# MCU.net
KiCad netlist of a schematic drawn in Altium Designer
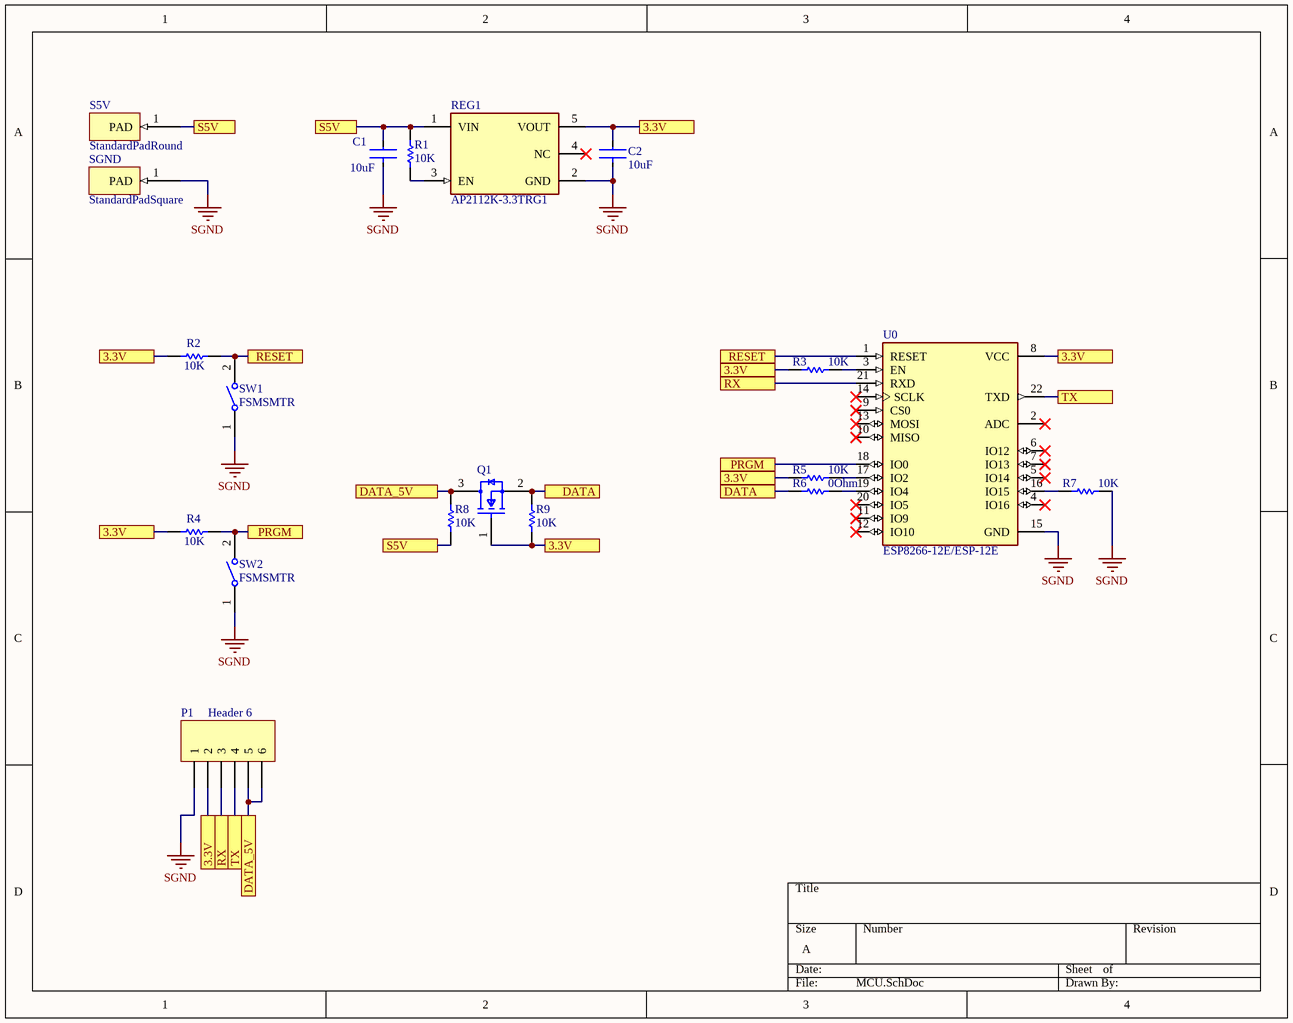
[diagram p0: MCU.SchDoc]

(export (version "E")
  (design (tool "Eeschema 10.0.6"))
  (components
    (comp (ref "C1")
      (value "10uF")
      (footprint "FP-CC0805-0_85-MFG")
      (description "CAP CER 1UF 10V X7R 0805")
      (fields
        (field (name "MANUFACTURER") "Yageo")
        (field (name "OCTOPART") "https://octopart.com/cc0805kkx7r6bb105-yageo-42522859")
      )
      (libsource (lib "Altium Content Vault") (part "11868f565c42a9108669ba33697ecf6"))
    )
    (comp (ref "C2")
      (value "10uF")
      (footprint "FP-CC0805-0_85-MFG")
      (description "CAP CER 1UF 10V X7R 0805")
      (fields
        (field (name "MANUFACTURER") "Yageo")
        (field (name "OCTOPART") "https://octopart.com/cc0805kkx7r6bb105-yageo-42522859")
      )
      (libsource (lib "Altium Content Vault") (part "11868f565c42a9108669ba33697ecf6"))
    )
    (comp (ref "P1")
      (value "Header 6")
      (footprint "HDR1X6")
      (description "Header, 6-Pin")
      (fields (field (name "PUBLISHER") "Altium Limited"))
      (libsource (lib "Gannon University") (part "Symbol"))
    )
    (comp (ref "Q1")
      (value "BSS138")
      (footprint "FP-318-08-IPC_B")
      (description "MOSFET N-CH 50V 220MA SOT-23")
      (libsource (lib "Altium Content Vault") (part "3b9c635fedb024a5347a57b145af9cc"))
    )
    (comp (ref "R1")
      (value "10K")
      (footprint "RESC2013X50X30LL20T20")
      (description "0805")
      (fields (field (name "MANUFACTURER") "Vishay Dale") (field (name "PART NUMBER") "CRCW08050000Z0EA"))
      (libsource (lib "Altium Content Vault") (part "RES"))
    )
    (comp (ref "R2")
      (value "10K")
      (footprint "RESC2013X50X30LL20T20")
      (description "0805")
      (fields (field (name "MANUFACTURER") "Vishay Dale") (field (name "PART NUMBER") "CRCW08050000Z0EA"))
      (libsource (lib "Altium Content Vault") (part "RES"))
    )
    (comp (ref "R3")
      (value "10K")
      (footprint "RESC2013X50X30LL20T20")
      (description "0805")
      (fields (field (name "MANUFACTURER") "Vishay Dale") (field (name "PART NUMBER") "CRCW08050000Z0EA"))
      (libsource (lib "Altium Content Vault") (part "RES"))
    )
    (comp (ref "R4")
      (value "10K")
      (footprint "RESC2013X50X30LL20T20")
      (description "0805")
      (fields (field (name "MANUFACTURER") "Vishay Dale") (field (name "PART NUMBER") "CRCW08050000Z0EA"))
      (libsource (lib "Altium Content Vault") (part "RES"))
    )
    (comp (ref "R5")
      (value "10K")
      (footprint "RESC2013X50X30LL20T20")
      (description "0805")
      (fields (field (name "MANUFACTURER") "Vishay Dale") (field (name "PART NUMBER") "CRCW08050000Z0EA"))
      (libsource (lib "Altium Content Vault") (part "RES"))
    )
    (comp (ref "R6")
      (value "0Ohm")
      (footprint "RESC2013X50X30LL20T20")
      (description "0805")
      (fields (field (name "MANUFACTURER") "Vishay Dale") (field (name "PART NUMBER") "CRCW08050000Z0EA"))
      (libsource (lib "Altium Content Vault") (part "RES"))
    )
    (comp (ref "R7")
      (value "10K")
      (footprint "RESC2013X50X30LL20T20")
      (description "0805")
      (fields (field (name "MANUFACTURER") "Vishay Dale") (field (name "PART NUMBER") "CRCW08050000Z0EA"))
      (libsource (lib "Altium Content Vault") (part "RES"))
    )
    (comp (ref "R8")
      (value "10K")
      (footprint "RESC2013X50X30ML20T20")
      (fields (field (name "PART NUMBER") "CRCW0805270RFKEA") (field (name "MANUFACTURER") "Vishay Dale"))
      (libsource (lib "Altium Content Vault") (part "RES"))
    )
    (comp (ref "R9")
      (value "10K")
      (footprint "RESC2013X50X30ML20T20")
      (fields (field (name "PART NUMBER") "CRCW0805270RFKEA") (field (name "MANUFACTURER") "Vishay Dale"))
      (libsource (lib "Altium Content Vault") (part "RES"))
    )
    (comp (ref "REG1")
      (value "AP2112K-3.3TRG1")
      (footprint "FP-SOT25-IPC_A")
      (description "IC REG LINEAR 3.3V 600MA SOT25")
      (libsource (lib "Altium Content Vault") (part "c8ab751aee5229183125ab046a11caa"))
    )
    (comp (ref "S5V")
      (value "StandardPadRound")
      (footprint "StandardPadRound-Footprint-1")
      (description "1.9mm x 1.9mm round pad with a 1mm hole")
      (libsource (lib "Gannon University") (part "StandardPadRound"))
    )
    (comp (ref "SGND")
      (value "StandardPadSquare")
      (footprint "StandardPadSquare-Footprint-1")
      (description "1.9mm X 1.9mm square pad with 1mm hole")
      (libsource (lib "Gannon University") (part "StandardPadSquare"))
    )
    (comp (ref "SW1")
      (value "FSMSMTR")
      (footprint "TECO-FSMSMTR_V")
      (description "FSMSM Push Button Switch, 50 mA, -35 to 85 degC, 2-Pin SMD, RoHS, Tape and Reel")
      (fields (field (name "MANUFACTURER") "TE Connectivity"))
      (libsource (lib "Altium Content Vault") (part "SW-SPST-2_C"))
    )
    (comp (ref "SW2")
      (value "FSMSMTR")
      (footprint "TECO-FSMSMTR_V")
      (description "FSMSM Push Button Switch, 50 mA, -35 to 85 degC, 2-Pin SMD, RoHS, Tape and Reel")
      (fields (field (name "MANUFACTURER") "TE Connectivity"))
      (libsource (lib "Altium Content Vault") (part "SW-SPST-2_C"))
    )
    (comp (ref "U0")
      (value "ESP8266-12E/ESP-12E")
      (footprint "XCVR_ESP8266-12E%2FESP-12E")
      (fields (field (name "MF") "AI-Thinker"))
      (libsource (lib "Gannon University") (part "ESP8266-12E/ESP-12E"))
    )
  )
  (nets
    (net (code "1") (name "/3.3V") (class "Default")
      (node (ref "C2") (pin "2") (pinfunction "2_2") (pintype "passive"))
      (node (ref "P1") (pin "2") (pinfunction "2_2") (pintype "passive"))
      (node (ref "Q1") (pin "1") (pinfunction "G_1") (pintype "passive"))
      (node (ref "R2") (pin "1") (pinfunction "1_1") (pintype "passive"))
      (node (ref "R3") (pin "1") (pinfunction "1_1") (pintype "passive"))
      (node (ref "R4") (pin "1") (pinfunction "1_1") (pintype "passive"))
      (node (ref "R5") (pin "1") (pinfunction "1_1") (pintype "passive"))
      (node (ref "R9") (pin "1") (pinfunction "1_1") (pintype "passive"))
      (node (ref "REG1") (pin "5") (pinfunction "VOUT_5") (pintype "power_in"))
      (node (ref "U0") (pin "8") (pinfunction "VCC_8") (pintype "power_in"))
    )
    (net (code "2") (name "/DATA") (class "Default")
      (node (ref "Q1") (pin "2") (pinfunction "S_2") (pintype "passive"))
      (node (ref "R6") (pin "1") (pinfunction "1_1") (pintype "passive"))
      (node (ref "R9") (pin "2") (pinfunction "2_2") (pintype "passive"))
    )
    (net (code "3") (name "/DATA_5V") (class "Default")
      (node (ref "P1") (pin "5") (pinfunction "5_5") (pintype "passive"))
      (node (ref "P1") (pin "6") (pinfunction "6_6") (pintype "passive"))
      (node (ref "Q1") (pin "3") (pinfunction "D_3") (pintype "passive"))
      (node (ref "R8") (pin "2") (pinfunction "2_2") (pintype "passive"))
    )
    (net (code "4") (name "/PRGM") (class "Default")
      (node (ref "R4") (pin "2") (pinfunction "2_2") (pintype "passive"))
      (node (ref "SW2") (pin "2") (pinfunction "2_2") (pintype "passive"))
      (node (ref "U0") (pin "18") (pinfunction "IO0_18") (pintype "bidirectional"))
    )
    (net (code "5") (name "/RESET") (class "Default")
      (node (ref "R2") (pin "2") (pinfunction "2_2") (pintype "passive"))
      (node (ref "SW1") (pin "2") (pinfunction "2_2") (pintype "passive"))
      (node (ref "U0") (pin "1") (pinfunction "RESET_1") (pintype "input"))
    )
    (net (code "6") (name "/RX") (class "Default")
      (node (ref "P1") (pin "3") (pinfunction "3_3") (pintype "passive"))
      (node (ref "U0") (pin "21") (pinfunction "RXD_21") (pintype "input"))
    )
    (net (code "7") (name "/S5V") (class "Default")
      (node (ref "C1") (pin "2") (pinfunction "2_2") (pintype "passive"))
      (node (ref "R1") (pin "2") (pinfunction "2_2") (pintype "passive"))
      (node (ref "R8") (pin "1") (pinfunction "1_1") (pintype "passive"))
      (node (ref "REG1") (pin "1") (pinfunction "VIN_1") (pintype "power_in"))
      (node (ref "S5V") (pin "1") (pinfunction "PAD_1") (pintype "input"))
    )
    (net (code "8") (name "/TX") (class "Default")
      (node (ref "P1") (pin "4") (pinfunction "4_4") (pintype "passive"))
      (node (ref "U0") (pin "22") (pinfunction "TXD_22") (pintype "output"))
    )
    (net (code "9") (name "Net-(REG1-EN)") (class "Default")
      (node (ref "R1") (pin "1") (pinfunction "1_1") (pintype "passive"))
      (node (ref "REG1") (pin "3") (pinfunction "EN_3") (pintype "input"))
    )
    (net (code "10") (name "Net-(U0-EN)") (class "Default")
      (node (ref "R3") (pin "2") (pinfunction "2_2") (pintype "passive"))
      (node (ref "U0") (pin "3") (pinfunction "EN_3") (pintype "input"))
    )
    (net (code "11") (name "Net-(U0-IO2)") (class "Default")
      (node (ref "R5") (pin "2") (pinfunction "2_2") (pintype "passive"))
      (node (ref "U0") (pin "17") (pinfunction "IO2_17") (pintype "bidirectional"))
    )
    (net (code "12") (name "Net-(U0-IO4)") (class "Default")
      (node (ref "R6") (pin "2") (pinfunction "2_2") (pintype "passive"))
      (node (ref "U0") (pin "19") (pinfunction "IO4_19") (pintype "bidirectional"))
    )
    (net (code "13") (name "Net-(U0-IO15)") (class "Default")
      (node (ref "R7") (pin "1") (pinfunction "1_1") (pintype "passive"))
      (node (ref "U0") (pin "16") (pinfunction "IO15_16") (pintype "bidirectional"))
    )
    (net (code "14") (name "SGND") (class "Default")
      (node (ref "C1") (pin "1") (pinfunction "1_1") (pintype "passive"))
      (node (ref "C2") (pin "1") (pinfunction "1_1") (pintype "passive"))
      (node (ref "P1") (pin "1") (pinfunction "1_1") (pintype "passive"))
      (node (ref "R7") (pin "2") (pinfunction "2_2") (pintype "passive"))
      (node (ref "REG1") (pin "2") (pinfunction "GND_2") (pintype "power_in"))
      (node (ref "SGND") (pin "1") (pinfunction "PAD_1") (pintype "input"))
      (node (ref "SW1") (pin "1") (pinfunction "1_1") (pintype "passive"))
      (node (ref "SW2") (pin "1") (pinfunction "1_1") (pintype "passive"))
      (node (ref "U0") (pin "15") (pinfunction "GND_15") (pintype "power_in"))
    )
    (net (code "15") (name "unconnected-(REG1-NC-Pad4)") (class "Default")
      (node (ref "REG1") (pin "4") (pinfunction "NC_4") (pintype "passive+no_connect"))
    )
    (net (code "16") (name "unconnected-(U0-ADC-Pad2)") (class "Default")
      (node (ref "U0") (pin "2") (pinfunction "ADC_2") (pintype "passive+no_connect"))
    )
    (net (code "17") (name "unconnected-(U0-CS0-Pad9)") (class "Default")
      (node (ref "U0") (pin "9") (pinfunction "CS0_9") (pintype "input+no_connect"))
    )
    (net (code "18") (name "unconnected-(U0-IO5-Pad20)") (class "Default")
      (node (ref "U0") (pin "20") (pinfunction "IO5_20") (pintype "bidirectional+no_connect"))
    )
    (net (code "19") (name "unconnected-(U0-IO9-Pad11)") (class "Default")
      (node (ref "U0") (pin "11") (pinfunction "IO9_11") (pintype "bidirectional+no_connect"))
    )
    (net (code "20") (name "unconnected-(U0-IO10-Pad12)") (class "Default")
      (node (ref "U0") (pin "12") (pinfunction "IO10_12") (pintype "bidirectional+no_connect"))
    )
    (net (code "21") (name "unconnected-(U0-IO12-Pad6)") (class "Default")
      (node (ref "U0") (pin "6") (pinfunction "IO12_6") (pintype "bidirectional+no_connect"))
    )
    (net (code "22") (name "unconnected-(U0-IO13-Pad7)") (class "Default")
      (node (ref "U0") (pin "7") (pinfunction "IO13_7") (pintype "bidirectional+no_connect"))
    )
    (net (code "23") (name "unconnected-(U0-IO14-Pad5)") (class "Default")
      (node (ref "U0") (pin "5") (pinfunction "IO14_5") (pintype "bidirectional+no_connect"))
    )
    (net (code "24") (name "unconnected-(U0-IO16-Pad4)") (class "Default")
      (node (ref "U0") (pin "4") (pinfunction "IO16_4") (pintype "bidirectional+no_connect"))
    )
    (net (code "25") (name "unconnected-(U0-MISO-Pad10)") (class "Default")
      (node (ref "U0") (pin "10") (pinfunction "MISO_10") (pintype "bidirectional+no_connect"))
    )
    (net (code "26") (name "unconnected-(U0-MOSI-Pad13)") (class "Default")
      (node (ref "U0") (pin "13") (pinfunction "MOSI_13") (pintype "bidirectional+no_connect"))
    )
    (net (code "27") (name "unconnected-(U0-SCLK-Pad14)") (class "Default")
      (node (ref "U0") (pin "14") (pinfunction "SCLK_14") (pintype "input+no_connect"))
    )
  )
)
